# ProPrj_Animatronic_Bird_Control_Carrier_.net
KiCad netlist of a schematic drawn in EasyEDA Pro
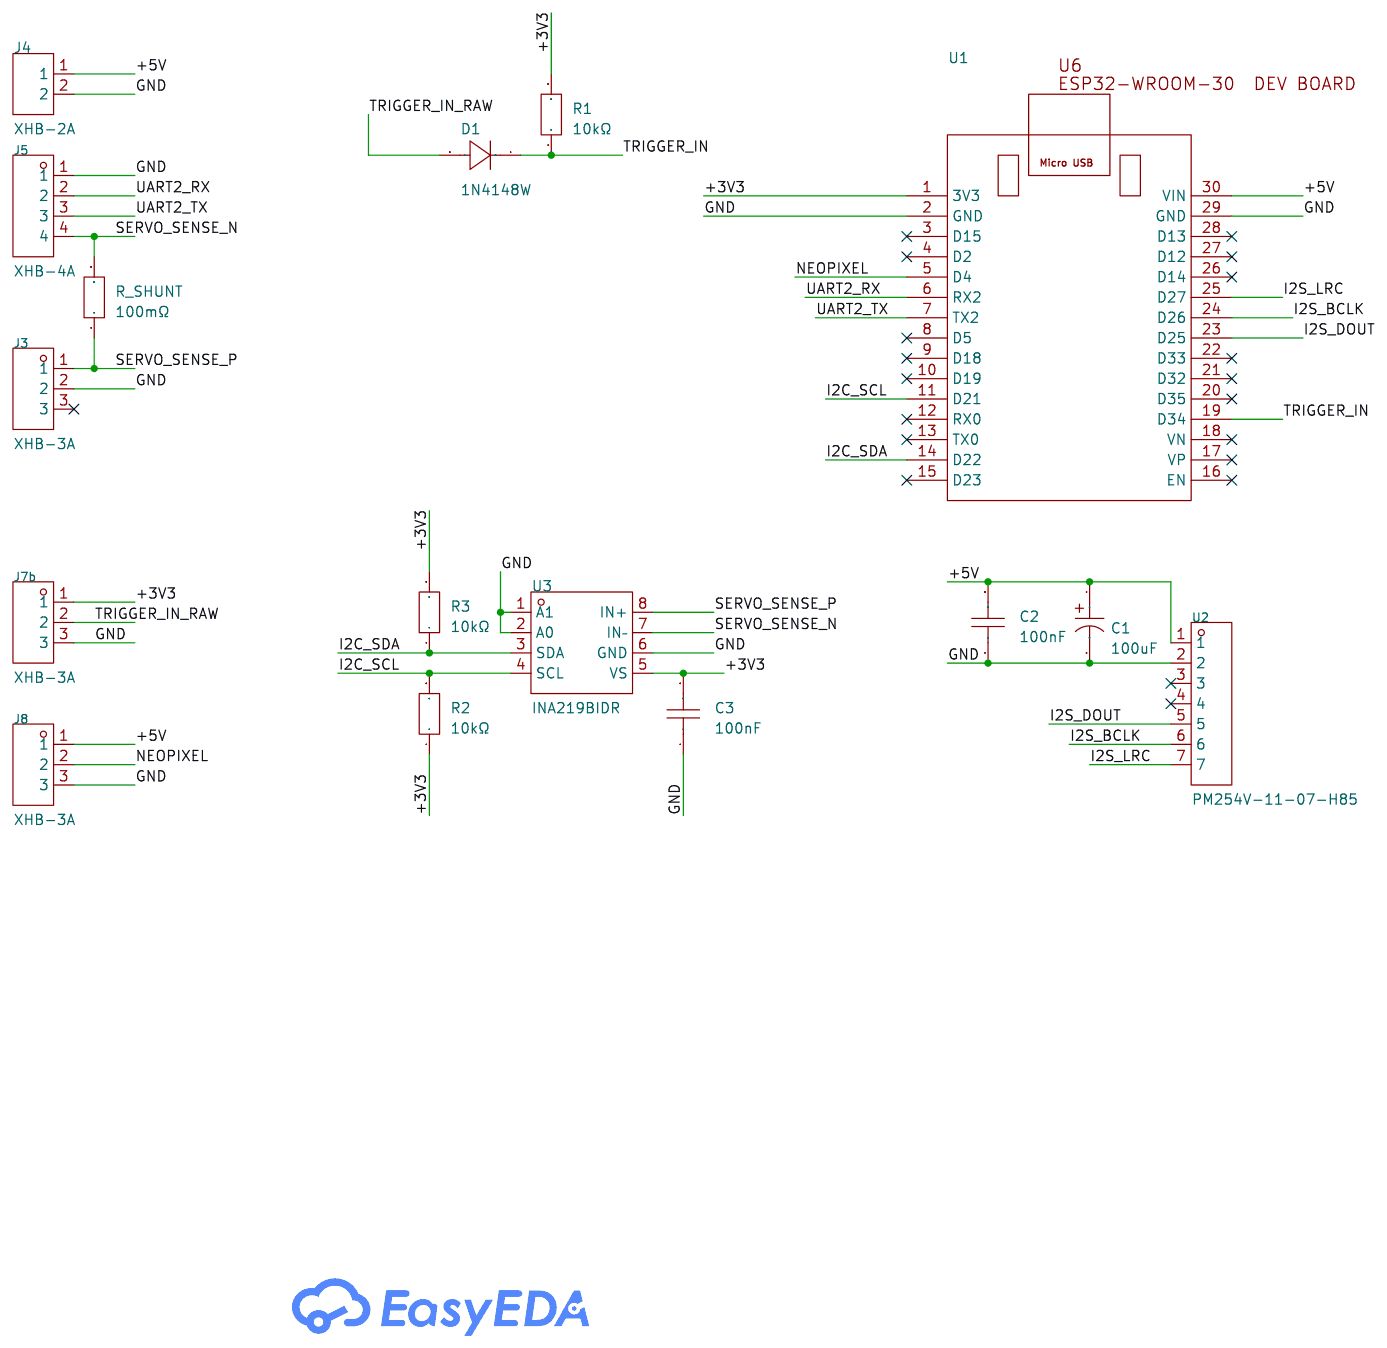
[diagram p0: schematic sheet]

(export (version "E")
  (design (tool "Eeschema 10.0.6"))
  (components
    (comp (ref "C1")
      (value "100uF")
      (footprint "easyedapro:CAP-SMD_BD6.3-L6.6-W6.6-FD")
      (fields (field (name "Manufacturer Part") "RST100UF16V003") (field (name "Manufacturer") "KNSCHA(科尼盛)"))
      (libsource (lib "easyedapro") (part "RST100UF16V003"))
    )
    (comp (ref "C2")
      (value "100nF")
      (footprint "easyedapro:C0603")
      (description "Capacitance:100nF Tolerance:±10% Tolerance:±10% Voltage Rating:50V Temperature Coefficient:X7R")
      (fields
        (field (name "Manufacturer Part") "CC0603KRX7R9BB104")
        (field (name "Manufacturer") "YAGEO(国巨)")
      )
      (libsource (lib "easyedapro") (part "CC0603KRX7R9BB104"))
    )
    (comp (ref "C3")
      (value "100nF")
      (footprint "easyedapro:C0603")
      (description "Capacitance:100nF Tolerance:±10% Tolerance:±10% Voltage Rating:50V Temperature Coefficient:X7R")
      (fields
        (field (name "Manufacturer Part") "CC0603KRX7R9BB104")
        (field (name "Manufacturer") "YAGEO(国巨)")
      )
      (libsource (lib "easyedapro") (part "CC0603KRX7R9BB104"))
    )
    (comp (ref "D1")
      (value "1N4148W")
      (footprint "easyedapro:SOD-123_L2.8-W1.8-LS3.7-RD-1")
      (fields (field (name "Manufacturer") "JSMSEMI(杰盛微)"))
      (libsource (lib "easyedapro") (part "1N4148W_C917030"))
    )
    (comp (ref "J3")
      (value "XHB-3A")
      (footprint "easyedapro:CONN-TH_XHB-3A")
      (fields (field (name "Manufacturer") "CAX(创都)"))
      (libsource (lib "easyedapro") (part "XHB-3A_C722899"))
    )
    (comp (ref "J4")
      (value "XHB-2A")
      (footprint "easyedapro:CONN-TH_XHB-2A_C2829622")
      (fields (field (name "Manufacturer") "FG(富港)"))
      (libsource (lib "easyedapro") (part "XHB-2A_C2829622"))
    )
    (comp (ref "J5")
      (value "XHB-4A")
      (footprint "easyedapro:CONN-TH_4P-P2.50_HCTL_HC-XHB-4A")
      (fields (field (name "Manufacturer") "DEALON(德艺隆)"))
      (libsource (lib "easyedapro") (part "XHB-4A_C2904971"))
    )
    (comp (ref "J7b")
      (value "XHB-3A")
      (footprint "easyedapro:CONN-TH_XHB-3A")
      (fields (field (name "Manufacturer") "CAX(创都)"))
      (libsource (lib "easyedapro") (part "XHB-3A_C722899"))
    )
    (comp (ref "J8")
      (value "XHB-3A")
      (footprint "easyedapro:CONN-TH_XHB-3A")
      (fields (field (name "Manufacturer") "CAX(创都)"))
      (libsource (lib "easyedapro") (part "XHB-3A_C722899"))
    )
    (comp (ref "R1")
      (value "10kΩ")
      (footprint "easyedapro:R0603")
      (fields (field (name "Manufacturer Part") "FRC0603J103 TS") (field (name "Manufacturer") "FOJAN(富捷)"))
      (libsource (lib "easyedapro") (part "FRC0603J103TS"))
    )
    (comp (ref "R2")
      (value "10kΩ")
      (footprint "easyedapro:R0603")
      (fields (field (name "Manufacturer Part") "FRC0603J103 TS") (field (name "Manufacturer") "FOJAN(富捷)"))
      (libsource (lib "easyedapro") (part "FRC0603J103TS"))
    )
    (comp (ref "R3")
      (value "10kΩ")
      (footprint "easyedapro:R0603")
      (fields (field (name "Manufacturer Part") "FRC0603J103 TS") (field (name "Manufacturer") "FOJAN(富捷)"))
      (libsource (lib "easyedapro") (part "FRC0603J103TS"))
    )
    (comp (ref "R_SHUNT")
      (value "100mΩ")
      (footprint "easyedapro:R2512")
      (fields (field (name "Manufacturer Part") "LRP12FTDSR100") (field (name "Manufacturer") "Viking(光颉)"))
      (libsource (lib "easyedapro") (part "LRP12FTDSR100"))
    )
    (comp (ref "U1")
      (value "~")
      (footprint "easyedapro:ESP32-WROOM-30-DEVBOARD")
      (libsource (lib "easyedapro") (part "ESP32-WROOM 30-pin dev board"))
    )
    (comp (ref "U2")
      (value "PM254V-11-07-H85")
      (footprint "easyedapro:HDR-TH_7P-P2.54-V-F")
      (fields (field (name "Manufacturer") "XFCN(兴飞)"))
      (libsource (lib "easyedapro") (part "PM254V-11-07-H85"))
    )
    (comp (ref "U3")
      (value "INA219BIDR")
      (footprint "easyedapro:SOIC-8_L5.0-W4.0-P1.27-LS6.1-BL")
      (fields (field (name "Manufacturer") "TI(德州仪器)"))
      (libsource (lib "easyedapro") (part "INA219BIDR"))
    )
  )
  (nets
    (net (code "1") (name "/+3V3") (class "Default")
      (node (ref "C3") (pin "2") (pinfunction "2_2") (pintype "unspecified"))
      (node (ref "J7b") (pin "1") (pinfunction "1_1") (pintype "input"))
      (node (ref "R1") (pin "2") (pinfunction "2_2") (pintype "unspecified"))
      (node (ref "R2") (pin "1") (pinfunction "1_1") (pintype "unspecified"))
      (node (ref "R3") (pin "2") (pinfunction "2_2") (pintype "unspecified"))
      (node (ref "U1") (pin "1") (pinfunction "3V3_1") (pintype "unspecified"))
      (node (ref "U3") (pin "5") (pinfunction "VS_5") (pintype "unspecified"))
    )
    (net (code "2") (name "/+5V") (class "Default")
      (node (ref "C1") (pin "1") (pinfunction "1_1") (pintype "input"))
      (node (ref "C2") (pin "2") (pinfunction "2_2") (pintype "unspecified"))
      (node (ref "J4") (pin "1") (pinfunction "1_1") (pintype "unspecified"))
      (node (ref "J8") (pin "1") (pinfunction "1_1") (pintype "input"))
      (node (ref "U1") (pin "30") (pinfunction "VIN_30") (pintype "unspecified"))
      (node (ref "U2") (pin "1") (pinfunction "1_1") (pintype "input"))
    )
    (net (code "3") (name "/GND") (class "Default")
      (node (ref "C1") (pin "2") (pinfunction "2_2") (pintype "input"))
      (node (ref "C2") (pin "1") (pinfunction "1_1") (pintype "unspecified"))
      (node (ref "C3") (pin "1") (pinfunction "1_1") (pintype "unspecified"))
      (node (ref "J3") (pin "2") (pinfunction "2_2") (pintype "input"))
      (node (ref "J4") (pin "2") (pinfunction "2_2") (pintype "unspecified"))
      (node (ref "J5") (pin "1") (pinfunction "1_1") (pintype "input"))
      (node (ref "J7b") (pin "3") (pinfunction "3_3") (pintype "input"))
      (node (ref "J8") (pin "3") (pinfunction "3_3") (pintype "input"))
      (node (ref "U1") (pin "2") (pinfunction "GND_2") (pintype "unspecified"))
      (node (ref "U1") (pin "29") (pinfunction "GND_29") (pintype "unspecified"))
      (node (ref "U2") (pin "2") (pinfunction "2_2") (pintype "input"))
      (node (ref "U3") (pin "1") (pinfunction "A1_1") (pintype "unspecified"))
      (node (ref "U3") (pin "2") (pinfunction "A0_2") (pintype "unspecified"))
      (node (ref "U3") (pin "6") (pinfunction "GND_6") (pintype "unspecified"))
    )
    (net (code "4") (name "/I2C_SCL") (class "Default")
      (node (ref "R2") (pin "2") (pinfunction "2_2") (pintype "unspecified"))
      (node (ref "U1") (pin "11") (pinfunction "D21_11") (pintype "unspecified"))
      (node (ref "U3") (pin "4") (pinfunction "SCL_4") (pintype "unspecified"))
    )
    (net (code "5") (name "/I2C_SDA") (class "Default")
      (node (ref "R3") (pin "1") (pinfunction "1_1") (pintype "unspecified"))
      (node (ref "U1") (pin "14") (pinfunction "D22_14") (pintype "unspecified"))
      (node (ref "U3") (pin "3") (pinfunction "SDA_3") (pintype "unspecified"))
    )
    (net (code "6") (name "/I2S_BCLK") (class "Default")
      (node (ref "U1") (pin "24") (pinfunction "D26_24") (pintype "unspecified"))
      (node (ref "U2") (pin "6") (pinfunction "6_6") (pintype "input"))
    )
    (net (code "7") (name "/I2S_DOUT") (class "Default")
      (node (ref "U1") (pin "23") (pinfunction "D25_23") (pintype "unspecified"))
      (node (ref "U2") (pin "5") (pinfunction "5_5") (pintype "input"))
    )
    (net (code "8") (name "/I2S_LRC") (class "Default")
      (node (ref "U1") (pin "25") (pinfunction "D27_25") (pintype "unspecified"))
      (node (ref "U2") (pin "7") (pinfunction "7_7") (pintype "input"))
    )
    (net (code "9") (name "/NEOPIXEL") (class "Default")
      (node (ref "J8") (pin "2") (pinfunction "2_2") (pintype "input"))
      (node (ref "U1") (pin "5") (pinfunction "D4_5") (pintype "unspecified"))
    )
    (net (code "10") (name "/SERVO_SENSE_N") (class "Default")
      (node (ref "J5") (pin "4") (pinfunction "4_4") (pintype "input"))
      (node (ref "R_SHUNT") (pin "2") (pinfunction "2_2") (pintype "unspecified"))
      (node (ref "U3") (pin "7") (pinfunction "IN–_7") (pintype "unspecified"))
    )
    (net (code "11") (name "/SERVO_SENSE_P") (class "Default")
      (node (ref "J3") (pin "1") (pinfunction "1_1") (pintype "input"))
      (node (ref "R_SHUNT") (pin "1") (pinfunction "1_1") (pintype "unspecified"))
      (node (ref "U3") (pin "8") (pinfunction "IN+_8") (pintype "unspecified"))
    )
    (net (code "12") (name "/TRIGGER_IN") (class "Default")
      (node (ref "D1") (pin "1") (pinfunction "C_1") (pintype "unspecified"))
      (node (ref "R1") (pin "1") (pinfunction "1_1") (pintype "unspecified"))
      (node (ref "U1") (pin "19") (pinfunction "D34_19") (pintype "unspecified"))
    )
    (net (code "13") (name "/TRIGGER_IN_RAW") (class "Default")
      (node (ref "D1") (pin "2") (pinfunction "A_2") (pintype "unspecified"))
      (node (ref "J7b") (pin "2") (pinfunction "2_2") (pintype "input"))
    )
    (net (code "14") (name "/UART2_RX") (class "Default")
      (node (ref "J5") (pin "2") (pinfunction "2_2") (pintype "input"))
      (node (ref "U1") (pin "6") (pinfunction "RX2_6") (pintype "unspecified"))
    )
    (net (code "15") (name "/UART2_TX") (class "Default")
      (node (ref "J5") (pin "3") (pinfunction "3_3") (pintype "input"))
      (node (ref "U1") (pin "7") (pinfunction "TX2_7") (pintype "unspecified"))
    )
    (net (code "16") (name "unconnected-(J3-Pad3)") (class "Default")
      (node (ref "J3") (pin "3") (pinfunction "3_3") (pintype "input+no_connect"))
    )
    (net (code "17") (name "unconnected-(U1-D2-Pad4)") (class "Default")
      (node (ref "U1") (pin "4") (pinfunction "D2_4") (pintype "unspecified+no_connect"))
    )
    (net (code "18") (name "unconnected-(U1-D5-Pad8)") (class "Default")
      (node (ref "U1") (pin "8") (pinfunction "D5_8") (pintype "unspecified+no_connect"))
    )
    (net (code "19") (name "unconnected-(U1-D12-Pad27)") (class "Default")
      (node (ref "U1") (pin "27") (pinfunction "D12_27") (pintype "unspecified+no_connect"))
    )
    (net (code "20") (name "unconnected-(U1-D13-Pad28)") (class "Default")
      (node (ref "U1") (pin "28") (pinfunction "D13_28") (pintype "unspecified+no_connect"))
    )
    (net (code "21") (name "unconnected-(U1-D14-Pad26)") (class "Default")
      (node (ref "U1") (pin "26") (pinfunction "D14_26") (pintype "unspecified+no_connect"))
    )
    (net (code "22") (name "unconnected-(U1-D15-Pad3)") (class "Default")
      (node (ref "U1") (pin "3") (pinfunction "D15_3") (pintype "unspecified+no_connect"))
    )
    (net (code "23") (name "unconnected-(U1-D18-Pad9)") (class "Default")
      (node (ref "U1") (pin "9") (pinfunction "D18_9") (pintype "unspecified+no_connect"))
    )
    (net (code "24") (name "unconnected-(U1-D19-Pad10)") (class "Default")
      (node (ref "U1") (pin "10") (pinfunction "D19_10") (pintype "unspecified+no_connect"))
    )
    (net (code "25") (name "unconnected-(U1-D23-Pad15)") (class "Default")
      (node (ref "U1") (pin "15") (pinfunction "D23_15") (pintype "unspecified+no_connect"))
    )
    (net (code "26") (name "unconnected-(U1-D32-Pad21)") (class "Default")
      (node (ref "U1") (pin "21") (pinfunction "D32_21") (pintype "unspecified+no_connect"))
    )
    (net (code "27") (name "unconnected-(U1-D33-Pad22)") (class "Default")
      (node (ref "U1") (pin "22") (pinfunction "D33_22") (pintype "unspecified+no_connect"))
    )
    (net (code "28") (name "unconnected-(U1-D35-Pad20)") (class "Default")
      (node (ref "U1") (pin "20") (pinfunction "D35_20") (pintype "unspecified+no_connect"))
    )
    (net (code "29") (name "unconnected-(U1-EN-Pad16)") (class "Default")
      (node (ref "U1") (pin "16") (pinfunction "EN_16") (pintype "unspecified+no_connect"))
    )
    (net (code "30") (name "unconnected-(U1-RX0-Pad12)") (class "Default")
      (node (ref "U1") (pin "12") (pinfunction "RX0_12") (pintype "unspecified+no_connect"))
    )
    (net (code "31") (name "unconnected-(U1-TX0-Pad13)") (class "Default")
      (node (ref "U1") (pin "13") (pinfunction "TX0_13") (pintype "unspecified+no_connect"))
    )
    (net (code "32") (name "unconnected-(U1-VN-Pad18)") (class "Default")
      (node (ref "U1") (pin "18") (pinfunction "VN_18") (pintype "unspecified+no_connect"))
    )
    (net (code "33") (name "unconnected-(U1-VP-Pad17)") (class "Default")
      (node (ref "U1") (pin "17") (pinfunction "VP_17") (pintype "unspecified+no_connect"))
    )
    (net (code "34") (name "unconnected-(U2-Pad3)") (class "Default")
      (node (ref "U2") (pin "3") (pinfunction "3_3") (pintype "input+no_connect"))
    )
    (net (code "35") (name "unconnected-(U2-Pad4)") (class "Default")
      (node (ref "U2") (pin "4") (pinfunction "4_4") (pintype "input+no_connect"))
    )
  )
)
